# sensor.net
KiCad netlist of a schematic drawn in EAGLE
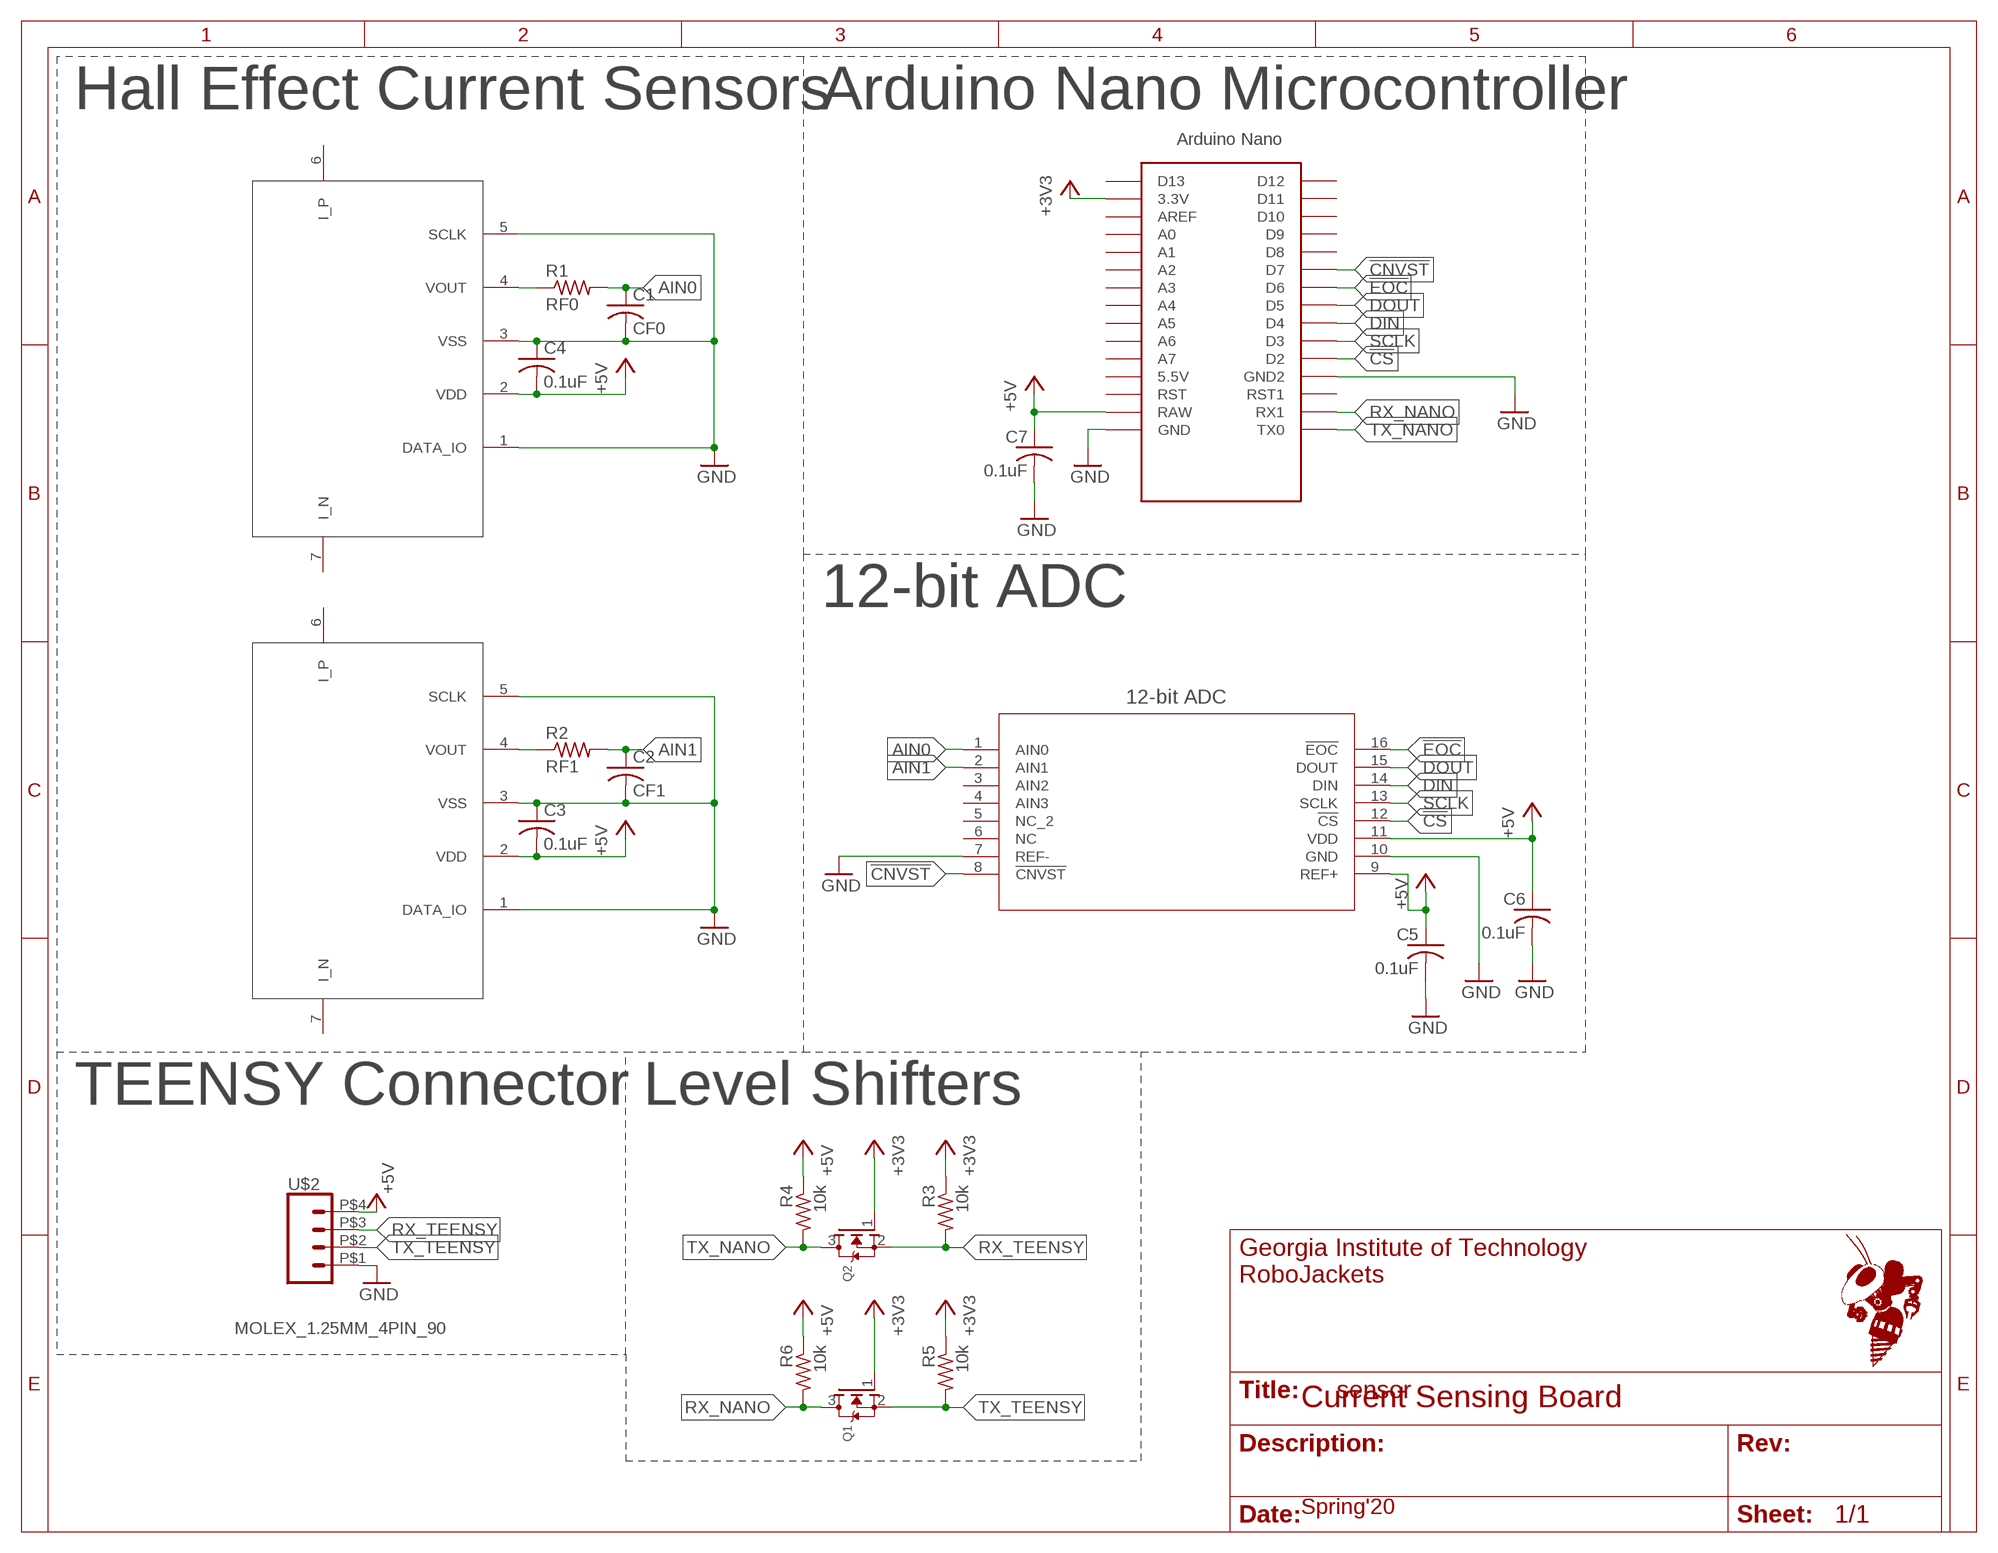
[diagram p0: schematic, sheet 1]

(export (version "E")
  (design (tool "Eeschema 10.0.6"))
  (components
    (comp (ref "12-BIT_ADC")
      (value "MAX11634EEE+T21-0055H_16-L")
      (footprint "eagle-import:21-0055H_16-L")
      (fields (field (name "MANUFACTURER_PART_NUMBER") "MAX11634EEE+T"))
      (libsource (lib "eagle-import") (part "MAX11634EEE+T21-0055H_16-L"))
    )
    (comp (ref "C1")
      (value "CF0")
      (footprint "eagle-import:C0603")
      (libsource (lib "eagle-import") (part "C-USC0603"))
    )
    (comp (ref "C2")
      (value "CF1")
      (footprint "eagle-import:C0603")
      (libsource (lib "eagle-import") (part "C-USC0603"))
    )
    (comp (ref "C3")
      (value "0.1uF")
      (footprint "eagle-import:C0603")
      (libsource (lib "eagle-import") (part "C-USC0603"))
    )
    (comp (ref "C4")
      (value "0.1uF")
      (footprint "eagle-import:C0603")
      (libsource (lib "eagle-import") (part "C-USC0603"))
    )
    (comp (ref "C5")
      (value "0.1uF")
      (footprint "eagle-import:C0603")
      (libsource (lib "eagle-import") (part "C-USC0603"))
    )
    (comp (ref "C6")
      (value "0.1uF")
      (footprint "eagle-import:C0603")
      (libsource (lib "eagle-import") (part "C-USC0603"))
    )
    (comp (ref "C7")
      (value "0.1uF")
      (footprint "eagle-import:C0603")
      (libsource (lib "eagle-import") (part "C-USC0603"))
    )
    (comp (ref "Q1")
      (value "ADAFRUIT_MOSFET-NREFLOW")
      (footprint "eagle-import:ADAFRUIT_SOT23")
      (libsource (lib "eagle-import") (part "ADAFRUIT_MOSFET-NREFLOW"))
    )
    (comp (ref "Q2")
      (value "ADAFRUIT_MOSFET-NREFLOW")
      (footprint "eagle-import:ADAFRUIT_SOT23")
      (libsource (lib "eagle-import") (part "ADAFRUIT_MOSFET-NREFLOW"))
    )
    (comp (ref "R1")
      (value "RF0")
      (footprint "eagle-import:R0603")
      (libsource (lib "eagle-import") (part "R-US_R0603"))
    )
    (comp (ref "R2")
      (value "RF1")
      (footprint "eagle-import:R0603")
      (libsource (lib "eagle-import") (part "R-US_R0603"))
    )
    (comp (ref "R3")
      (value "10k")
      (footprint "eagle-import:R0603")
      (libsource (lib "eagle-import") (part "R-US_R0603"))
    )
    (comp (ref "R4")
      (value "10k")
      (footprint "eagle-import:R0603")
      (libsource (lib "eagle-import") (part "R-US_R0603"))
    )
    (comp (ref "R5")
      (value "10k")
      (footprint "eagle-import:R0603")
      (libsource (lib "eagle-import") (part "R-US_R0603"))
    )
    (comp (ref "R6")
      (value "10k")
      (footprint "eagle-import:R0603")
      (libsource (lib "eagle-import") (part "R-US_R0603"))
    )
    (comp (ref "SENSOR_0")
      (value "CQ2065")
      (footprint "eagle-import:CQ2065")
      (libsource (lib "eagle-import") (part "CQ2065"))
    )
    (comp (ref "SENSOR_1")
      (value "CQ2065")
      (footprint "eagle-import:CQ2065")
      (libsource (lib "eagle-import") (part "CQ2065"))
    )
    (comp (ref "U$1")
      (value "NANO")
      (footprint "eagle-import:NANO")
      (libsource (lib "eagle-import") (part "NANO"))
    )
    (comp (ref "U$2")
      (value "MOLEX_1.25MM_4PIN_90")
      (footprint "eagle-import:MOLEX_1.25MM_4PIN_90")
      (libsource (lib "eagle-import") (part "MOLEX_1.25MM_4PIN_90"))
    )
  )
  (nets
    (net (code "1") (name "+3V3") (class "Default")
      (node (ref "Q1") (pin "1") (pinfunction "G_1") (pintype "bidirectional"))
      (node (ref "Q2") (pin "1") (pinfunction "G_1") (pintype "bidirectional"))
      (node (ref "R3") (pin "1") (pinfunction "1_1") (pintype "passive"))
      (node (ref "R5") (pin "1") (pinfunction "1_1") (pintype "passive"))
      (node (ref "U$1") (pin "3.3V") (pinfunction "3.3V_3.3V") (pintype "bidirectional"))
    )
    (net (code "2") (name "+5V") (class "Default")
      (node (ref "12-BIT_ADC") (pin "11") (pinfunction "VDD_11") (pintype "power_in"))
      (node (ref "12-BIT_ADC") (pin "9") (pinfunction "REF+_9") (pintype "passive"))
      (node (ref "C3") (pin "2") (pinfunction "2_2") (pintype "passive"))
      (node (ref "C4") (pin "2") (pinfunction "2_2") (pintype "passive"))
      (node (ref "C5") (pin "1") (pinfunction "1_1") (pintype "passive"))
      (node (ref "C6") (pin "1") (pinfunction "1_1") (pintype "passive"))
      (node (ref "C7") (pin "1") (pinfunction "1_1") (pintype "passive"))
      (node (ref "R4") (pin "1") (pinfunction "1_1") (pintype "passive"))
      (node (ref "R6") (pin "1") (pinfunction "1_1") (pintype "passive"))
      (node (ref "SENSOR_0") (pin "2") (pinfunction "VDD_2") (pintype "bidirectional"))
      (node (ref "SENSOR_1") (pin "2") (pinfunction "VDD_2") (pintype "bidirectional"))
      (node (ref "U$1") (pin "GND") (pinfunction "RAW_GND") (pintype "bidirectional"))
      (node (ref "U$2") (pin "P$4") (pinfunction "4_P$4") (pintype "passive"))
    )
    (net (code "3") (name "/~{CNVST}") (class "Default")
      (node (ref "12-BIT_ADC") (pin "8") (pinfunction "~{CNVST}_8") (pintype "passive"))
      (node (ref "U$1") (pin "D7") (pinfunction "D7_D7") (pintype "bidirectional"))
    )
    (net (code "4") (name "/~{CS}") (class "Default")
      (node (ref "12-BIT_ADC") (pin "12") (pinfunction "~{CS}_12") (pintype "passive"))
      (node (ref "U$1") (pin "D2") (pinfunction "D2_D2") (pintype "bidirectional"))
    )
    (net (code "5") (name "/~{EOC}") (class "Default")
      (node (ref "12-BIT_ADC") (pin "16") (pinfunction "~{EOC}_16") (pintype "passive"))
      (node (ref "U$1") (pin "D6") (pinfunction "D6_D6") (pintype "bidirectional"))
    )
    (net (code "6") (name "AIN0") (class "Default")
      (node (ref "12-BIT_ADC") (pin "1") (pinfunction "AIN0_1") (pintype "input"))
      (node (ref "C1") (pin "1") (pinfunction "1_1") (pintype "passive"))
      (node (ref "R1") (pin "2") (pinfunction "2_2") (pintype "passive"))
    )
    (net (code "7") (name "AIN1") (class "Default")
      (node (ref "12-BIT_ADC") (pin "2") (pinfunction "AIN1_2") (pintype "input"))
      (node (ref "C2") (pin "1") (pinfunction "1_1") (pintype "passive"))
      (node (ref "R2") (pin "2") (pinfunction "2_2") (pintype "passive"))
    )
    (net (code "8") (name "DIN") (class "Default")
      (node (ref "12-BIT_ADC") (pin "14") (pinfunction "DIN_14") (pintype "input"))
      (node (ref "U$1") (pin "D4") (pinfunction "D4_D4") (pintype "bidirectional"))
    )
    (net (code "9") (name "DOUT") (class "Default")
      (node (ref "12-BIT_ADC") (pin "15") (pinfunction "DOUT_15") (pintype "output"))
      (node (ref "U$1") (pin "D5") (pinfunction "D5_D5") (pintype "bidirectional"))
    )
    (net (code "10") (name "GND") (class "Default")
      (node (ref "12-BIT_ADC") (pin "10") (pinfunction "GND_10") (pintype "power_in"))
      (node (ref "12-BIT_ADC") (pin "7") (pinfunction "REF-_7") (pintype "passive"))
      (node (ref "C1") (pin "2") (pinfunction "2_2") (pintype "passive"))
      (node (ref "C2") (pin "2") (pinfunction "2_2") (pintype "passive"))
      (node (ref "C3") (pin "1") (pinfunction "1_1") (pintype "passive"))
      (node (ref "C4") (pin "1") (pinfunction "1_1") (pintype "passive"))
      (node (ref "C5") (pin "2") (pinfunction "2_2") (pintype "passive"))
      (node (ref "C6") (pin "2") (pinfunction "2_2") (pintype "passive"))
      (node (ref "C7") (pin "2") (pinfunction "2_2") (pintype "passive"))
      (node (ref "SENSOR_0") (pin "1") (pinfunction "DATA_IO_1") (pintype "bidirectional"))
      (node (ref "SENSOR_0") (pin "3") (pinfunction "VSS_3") (pintype "bidirectional"))
      (node (ref "SENSOR_0") (pin "5") (pinfunction "SCLK_5") (pintype "bidirectional"))
      (node (ref "SENSOR_1") (pin "1") (pinfunction "DATA_IO_1") (pintype "bidirectional"))
      (node (ref "SENSOR_1") (pin "3") (pinfunction "VSS_3") (pintype "bidirectional"))
      (node (ref "SENSOR_1") (pin "5") (pinfunction "SCLK_5") (pintype "bidirectional"))
      (node (ref "U$1") (pin "GND1") (pinfunction "GND2_GND1") (pintype "bidirectional"))
      (node (ref "U$1") (pin "RAW") (pinfunction "GND_RAW") (pintype "bidirectional"))
      (node (ref "U$2") (pin "P$1") (pinfunction "1_P$1") (pintype "passive"))
    )
    (net (code "11") (name "Net-(SENSOR_0-VOUT)") (class "Default")
      (node (ref "R1") (pin "1") (pinfunction "1_1") (pintype "passive"))
      (node (ref "SENSOR_0") (pin "4") (pinfunction "VOUT_4") (pintype "bidirectional"))
    )
    (net (code "12") (name "Net-(SENSOR_1-VOUT)") (class "Default")
      (node (ref "R2") (pin "1") (pinfunction "1_1") (pintype "passive"))
      (node (ref "SENSOR_1") (pin "4") (pinfunction "VOUT_4") (pintype "bidirectional"))
    )
    (net (code "13") (name "RX_NANO") (class "Default")
      (node (ref "Q1") (pin "3") (pinfunction "D_3") (pintype "bidirectional"))
      (node (ref "R6") (pin "2") (pinfunction "2_2") (pintype "passive"))
      (node (ref "U$1") (pin "RX1") (pinfunction "RX1_RX1") (pintype "bidirectional"))
    )
    (net (code "14") (name "RX_TEENSY") (class "Default")
      (node (ref "Q2") (pin "2") (pinfunction "S_2") (pintype "bidirectional"))
      (node (ref "R3") (pin "2") (pinfunction "2_2") (pintype "passive"))
      (node (ref "U$2") (pin "P$3") (pinfunction "3_P$3") (pintype "passive"))
    )
    (net (code "15") (name "SCLK") (class "Default")
      (node (ref "12-BIT_ADC") (pin "13") (pinfunction "SCLK_13") (pintype "passive"))
      (node (ref "U$1") (pin "D3") (pinfunction "D3_D3") (pintype "bidirectional"))
    )
    (net (code "16") (name "TX_NANO") (class "Default")
      (node (ref "Q2") (pin "3") (pinfunction "D_3") (pintype "bidirectional"))
      (node (ref "R4") (pin "2") (pinfunction "2_2") (pintype "passive"))
      (node (ref "U$1") (pin "TX0") (pinfunction "TX0_TX0") (pintype "bidirectional"))
    )
    (net (code "17") (name "TX_TEENSY") (class "Default")
      (node (ref "Q1") (pin "2") (pinfunction "S_2") (pintype "bidirectional"))
      (node (ref "R5") (pin "2") (pinfunction "2_2") (pintype "passive"))
      (node (ref "U$2") (pin "P$2") (pinfunction "2_P$2") (pintype "passive"))
    )
    (net (code "18") (name "unconnected-(12-BIT_ADC-AIN2-Pad3)") (class "Default")
      (node (ref "12-BIT_ADC") (pin "3") (pinfunction "AIN2_3") (pintype "input"))
    )
    (net (code "19") (name "unconnected-(12-BIT_ADC-AIN3-Pad4)") (class "Default")
      (node (ref "12-BIT_ADC") (pin "4") (pinfunction "AIN3_4") (pintype "input"))
    )
    (net (code "20") (name "unconnected-(12-BIT_ADC-NC-Pad6)") (class "Default")
      (node (ref "12-BIT_ADC") (pin "6") (pinfunction "NC_6") (pintype "passive"))
    )
    (net (code "21") (name "unconnected-(12-BIT_ADC-NC_2-Pad5)") (class "Default")
      (node (ref "12-BIT_ADC") (pin "5") (pinfunction "NC_2_5") (pintype "passive"))
    )
    (net (code "22") (name "unconnected-(SENSOR_0-I_N-Pad7)") (class "Default")
      (node (ref "SENSOR_0") (pin "7") (pinfunction "I_N_7") (pintype "bidirectional"))
    )
    (net (code "23") (name "unconnected-(SENSOR_0-I_P-Pad6)") (class "Default")
      (node (ref "SENSOR_0") (pin "6") (pinfunction "I_P_6") (pintype "bidirectional"))
    )
    (net (code "24") (name "unconnected-(SENSOR_1-I_N-Pad7)") (class "Default")
      (node (ref "SENSOR_1") (pin "7") (pinfunction "I_N_7") (pintype "bidirectional"))
    )
    (net (code "25") (name "unconnected-(SENSOR_1-I_P-Pad6)") (class "Default")
      (node (ref "SENSOR_1") (pin "6") (pinfunction "I_P_6") (pintype "bidirectional"))
    )
    (net (code "26") (name "unconnected-(U$1-5.5V-Pad5V)") (class "Default")
      (node (ref "U$1") (pin "5V") (pinfunction "5.5V_5V") (pintype "bidirectional"))
    )
    (net (code "27") (name "unconnected-(U$1-PadA0)") (class "Default")
      (node (ref "U$1") (pin "A0") (pinfunction "A0_A0") (pintype "bidirectional"))
    )
    (net (code "28") (name "unconnected-(U$1-PadA1)") (class "Default")
      (node (ref "U$1") (pin "A1") (pinfunction "A1_A1") (pintype "bidirectional"))
    )
    (net (code "29") (name "unconnected-(U$1-PadA2)") (class "Default")
      (node (ref "U$1") (pin "A2") (pinfunction "A2_A2") (pintype "bidirectional"))
    )
    (net (code "30") (name "unconnected-(U$1-PadA3)") (class "Default")
      (node (ref "U$1") (pin "A3") (pinfunction "A3_A3") (pintype "bidirectional"))
    )
    (net (code "31") (name "unconnected-(U$1-PadA4)") (class "Default")
      (node (ref "U$1") (pin "A4") (pinfunction "A4_A4") (pintype "bidirectional"))
    )
    (net (code "32") (name "unconnected-(U$1-PadA5)") (class "Default")
      (node (ref "U$1") (pin "A5") (pinfunction "A5_A5") (pintype "bidirectional"))
    )
    (net (code "33") (name "unconnected-(U$1-PadA6)") (class "Default")
      (node (ref "U$1") (pin "A6") (pinfunction "A6_A6") (pintype "bidirectional"))
    )
    (net (code "34") (name "unconnected-(U$1-PadA7)") (class "Default")
      (node (ref "U$1") (pin "A7") (pinfunction "A7_A7") (pintype "bidirectional"))
    )
    (net (code "35") (name "unconnected-(U$1-PadAREF)") (class "Default")
      (node (ref "U$1") (pin "AREF") (pinfunction "AREF_AREF") (pintype "bidirectional"))
    )
    (net (code "36") (name "unconnected-(U$1-PadD8)") (class "Default")
      (node (ref "U$1") (pin "D8") (pinfunction "D8_D8") (pintype "bidirectional"))
    )
    (net (code "37") (name "unconnected-(U$1-PadD9)") (class "Default")
      (node (ref "U$1") (pin "D9") (pinfunction "D9_D9") (pintype "bidirectional"))
    )
    (net (code "38") (name "unconnected-(U$1-PadD10)") (class "Default")
      (node (ref "U$1") (pin "D10") (pinfunction "D10_D10") (pintype "bidirectional"))
    )
    (net (code "39") (name "unconnected-(U$1-PadD11)") (class "Default")
      (node (ref "U$1") (pin "D11") (pinfunction "D11_D11") (pintype "bidirectional"))
    )
    (net (code "40") (name "unconnected-(U$1-PadD12)") (class "Default")
      (node (ref "U$1") (pin "D12") (pinfunction "D12_D12") (pintype "bidirectional"))
    )
    (net (code "41") (name "unconnected-(U$1-PadD13)") (class "Default")
      (node (ref "U$1") (pin "D13") (pinfunction "D13_D13") (pintype "bidirectional"))
    )
    (net (code "42") (name "unconnected-(U$1-PadICSP1)") (class "Default")
      (node (ref "U$1") (pin "ICSP1") (pinfunction "ICSP1_ICSP1") (pintype "bidirectional"))
    )
    (net (code "43") (name "unconnected-(U$1-PadICSP2)") (class "Default")
      (node (ref "U$1") (pin "ICSP2") (pinfunction "ICSP2_ICSP2") (pintype "bidirectional"))
    )
    (net (code "44") (name "unconnected-(U$1-PadICSP3)") (class "Default")
      (node (ref "U$1") (pin "ICSP3") (pinfunction "ICSP3_ICSP3") (pintype "bidirectional"))
    )
    (net (code "45") (name "unconnected-(U$1-PadICSP4)") (class "Default")
      (node (ref "U$1") (pin "ICSP4") (pinfunction "ICSP4_ICSP4") (pintype "bidirectional"))
    )
    (net (code "46") (name "unconnected-(U$1-PadICSP5)") (class "Default")
      (node (ref "U$1") (pin "ICSP5") (pinfunction "ICSP5_ICSP5") (pintype "bidirectional"))
    )
    (net (code "47") (name "unconnected-(U$1-PadICSP6)") (class "Default")
      (node (ref "U$1") (pin "ICSP6") (pinfunction "ICSP6_ICSP6") (pintype "bidirectional"))
    )
    (net (code "48") (name "unconnected-(U$1-PadRST)") (class "Default")
      (node (ref "U$1") (pin "RST") (pinfunction "RST_RST") (pintype "bidirectional"))
    )
    (net (code "49") (name "unconnected-(U$1-PadRST1)") (class "Default")
      (node (ref "U$1") (pin "RST1") (pinfunction "RST1_RST1") (pintype "bidirectional"))
    )
  )
)
